# ArduinoZero.net
KiCad netlist of a schematic drawn in Altium Designer
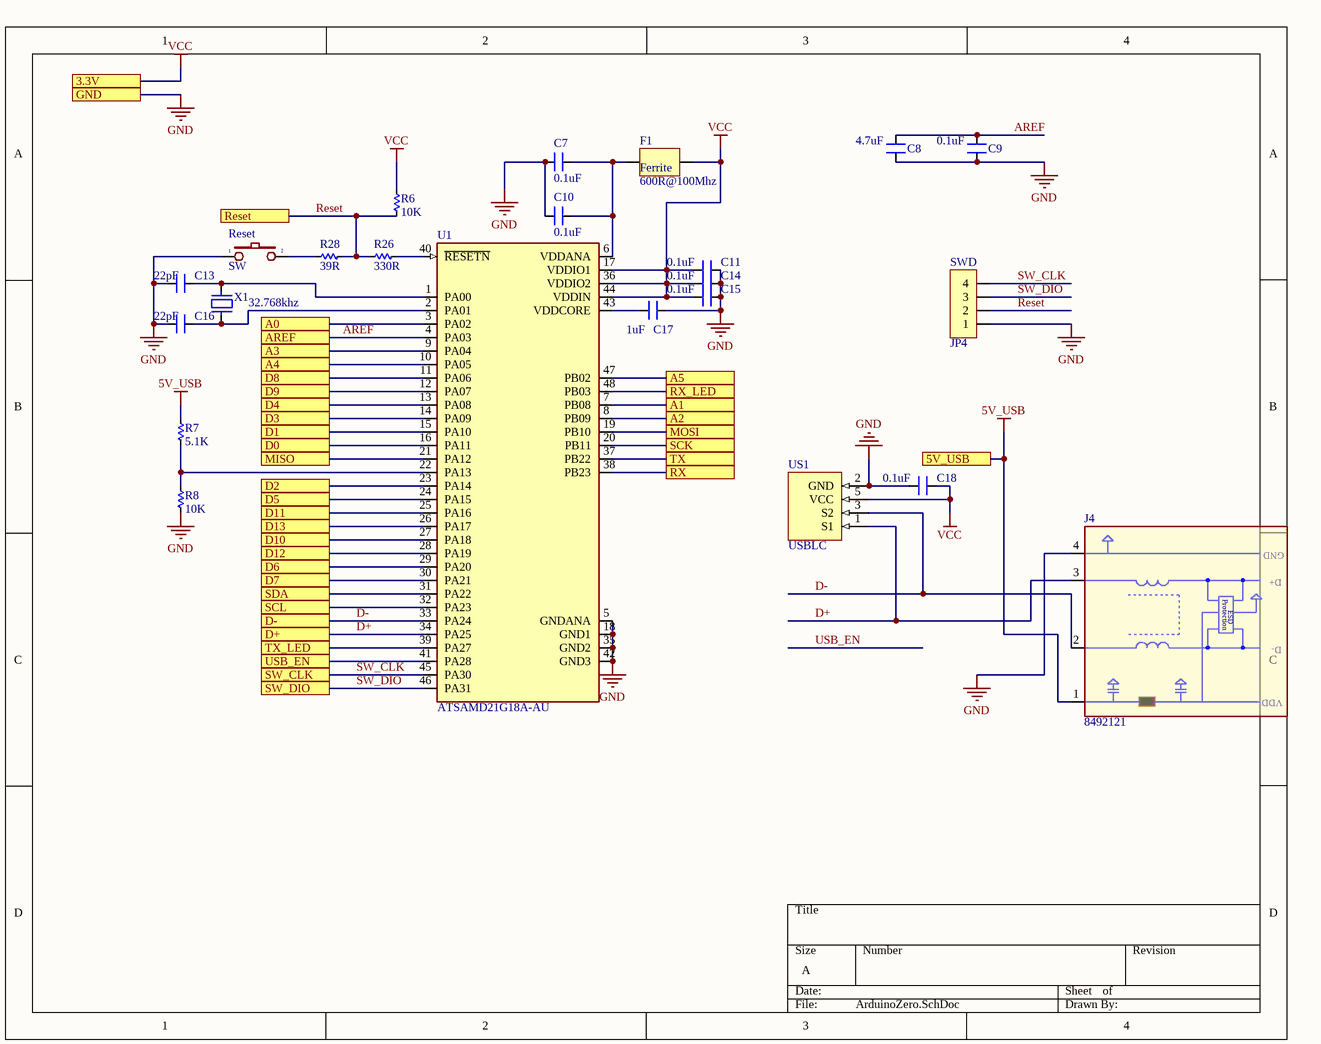
[diagram p0: ArduinoZero.SchDoc]

(export (version "E")
  (design (tool "Eeschema 10.0.6"))
  (components
    (comp (ref "C7") (value "0.1uF") (footprint "CN-SMD-0603_big") (libsource (lib "nhan") (part "CN")))
    (comp (ref "C8") (value "4.7uF") (footprint "CN-SMD-0603_big") (libsource (lib "nhan") (part "CN")))
    (comp (ref "C9") (value "0.1uF") (footprint "CN-SMD-0603_big") (libsource (lib "nhan") (part "CN")))
    (comp (ref "C10") (value "0.1uF") (footprint "CN-SMD-0603_big") (libsource (lib "nhan") (part "CN")))
    (comp (ref "C11") (value "0.1uF") (footprint "CN-SMD-0603_big") (libsource (lib "nhan") (part "CN")))
    (comp (ref "C13") (value "22pF") (footprint "CN-SMD-0603_big") (libsource (lib "nhan") (part "CN")))
    (comp (ref "C14") (value "0.1uF") (footprint "CN-SMD-0603_big") (libsource (lib "nhan") (part "CN")))
    (comp (ref "C15") (value "0.1uF") (footprint "CN-SMD-0603_big") (libsource (lib "nhan") (part "CN")))
    (comp (ref "C16") (value "22pF") (footprint "CN-SMD-0603_big") (libsource (lib "nhan") (part "CN")))
    (comp (ref "C17") (value "1uF") (footprint "CN-SMD-0603_big") (libsource (lib "nhan") (part "CN")))
    (comp (ref "C18") (value "0.1uF") (footprint "CN-SMD-0603_big") (libsource (lib "nhan") (part "CN")))
    (comp (ref "F1")
      (value "600R@100Mhz")
      (footprint "Capacitor_805")
      (libsource (lib "nhan") (part "Ferrite"))
    )
    (comp (ref "J4")
      (value "8492121")
      (footprint "USB-C3")
      (description "THT USB 2.0 A Connector WE-EPLE")
      (fields
        (field (name "MANUFACTURER") "Würth Elektronik eiSos GmbH")
        (field (name "CREATED BY") "Christin Otto")
      )
      (libsource (lib "BanLinhKien") (part "USB-4"))
    )
    (comp (ref "R6") (value "10K") (footprint "RES-SMD-0603_BIG") (libsource (lib "nhan") (part "R")))
    (comp (ref "R7") (value "5.1K") (footprint "RES-SMD-0603_BIG") (libsource (lib "nhan") (part "R")))
    (comp (ref "R8") (value "10K") (footprint "RES-SMD-0603_BIG") (libsource (lib "nhan") (part "R")))
    (comp (ref "R26") (value "330R") (footprint "RES-SMD-0603_BIG") (libsource (lib "nhan") (part "R")))
    (comp (ref "R28") (value "39R") (footprint "RES-SMD-0603_BIG") (libsource (lib "nhan") (part "R")))
    (comp (ref "Reset")
      (value "SW")
      (footprint "SW1-SMD")
      (description "Switch button 2 pin")
      (libsource (lib "BanLinhKien") (part "SW2"))
    )
    (comp (ref "SWD")
      (value "JP4")
      (footprint "JP4-D1C")
      (description "WR-PHD 2.54 mm Angled Socket Header")
      (fields
        (field (name "MANUFACTURER") "Würth Elektronik eiSos GmbH")
        (field (name "PARTNO") "613004143121")
        (field (name "CREATED BY") "Karrer Zheng")
      )
      (libsource (lib "BanLinhKien") (part "JP4"))
    )
    (comp (ref "U1")
      (value "ATSAMD21G18A-AU")
      (footprint "QFP50P900X900X120-48N")
      (fields (field (name "MF") "Microchip"))
      (libsource (lib "nhan") (part "ATSAMD21G18A-AU"))
    )
    (comp (ref "US1")
      (value "USBLC")
      (footprint "SOT23-6")
      (description "http://robocon.vn/detail/ic81-ic-dan-ul26-usblc6-2sc6-sot-23-6-st-st-esd.html")
      (libsource (lib "nhan") (part "USBLC6-2S"))
    )
    (comp (ref "X1")
      (value "32.768khz")
      (footprint "XT32k")
      (description "Crystal, 32.768 KHz, -40 to 85 degC, 3.2 x 1.5 x 0.9 mm SMD")
      (libsource (lib "BanLinhKien") (part "XT2"))
    )
  )
  (nets
    (net (code "1") (name "/A0") (class "Default")
      (node (ref "U1") (pin "3") (pinfunction "PA02_3") (pintype "bidirectional"))
    )
    (net (code "2") (name "/A1") (class "Default")
      (node (ref "U1") (pin "7") (pinfunction "PB08_7") (pintype "bidirectional"))
    )
    (net (code "3") (name "/A2") (class "Default")
      (node (ref "U1") (pin "8") (pinfunction "PB09_8") (pintype "bidirectional"))
    )
    (net (code "4") (name "/A3") (class "Default")
      (node (ref "U1") (pin "9") (pinfunction "PA04_9") (pintype "bidirectional"))
    )
    (net (code "5") (name "/A4") (class "Default")
      (node (ref "U1") (pin "10") (pinfunction "PA05_10") (pintype "bidirectional"))
    )
    (net (code "6") (name "/A5") (class "Default")
      (node (ref "U1") (pin "47") (pinfunction "PB02_47") (pintype "bidirectional"))
    )
    (net (code "7") (name "/AREF") (class "Default")
      (node (ref "C8") (pin "2") (pinfunction "2_2") (pintype "passive"))
      (node (ref "C9") (pin "2") (pinfunction "2_2") (pintype "passive"))
      (node (ref "U1") (pin "4") (pinfunction "PA03_4") (pintype "bidirectional"))
    )
    (net (code "8") (name "/D+") (class "Default")
      (node (ref "J4") (pin "3") (pinfunction "D+_3") (pintype "passive"))
      (node (ref "U1") (pin "34") (pinfunction "PA25_34") (pintype "bidirectional"))
      (node (ref "US1") (pin "1") (pinfunction "S1_1") (pintype "input"))
    )
    (net (code "9") (name "/D-") (class "Default")
      (node (ref "J4") (pin "2") (pinfunction "D-_2") (pintype "passive"))
      (node (ref "U1") (pin "33") (pinfunction "PA24_33") (pintype "bidirectional"))
      (node (ref "US1") (pin "3") (pinfunction "S2_3") (pintype "input"))
    )
    (net (code "10") (name "/D0") (class "Default")
      (node (ref "U1") (pin "16") (pinfunction "PA11_16") (pintype "bidirectional"))
    )
    (net (code "11") (name "/D1") (class "Default")
      (node (ref "U1") (pin "15") (pinfunction "PA10_15") (pintype "bidirectional"))
    )
    (net (code "12") (name "/D2") (class "Default")
      (node (ref "U1") (pin "23") (pinfunction "PA14_23") (pintype "bidirectional"))
    )
    (net (code "13") (name "/D3") (class "Default")
      (node (ref "U1") (pin "14") (pinfunction "PA09_14") (pintype "bidirectional"))
    )
    (net (code "14") (name "/D4") (class "Default")
      (node (ref "U1") (pin "13") (pinfunction "PA08_13") (pintype "bidirectional"))
    )
    (net (code "15") (name "/D5") (class "Default")
      (node (ref "U1") (pin "24") (pinfunction "PA15_24") (pintype "bidirectional"))
    )
    (net (code "16") (name "/D6") (class "Default")
      (node (ref "U1") (pin "29") (pinfunction "PA20_29") (pintype "bidirectional"))
    )
    (net (code "17") (name "/D7") (class "Default")
      (node (ref "U1") (pin "30") (pinfunction "PA21_30") (pintype "bidirectional"))
    )
    (net (code "18") (name "/D8") (class "Default")
      (node (ref "U1") (pin "11") (pinfunction "PA06_11") (pintype "bidirectional"))
    )
    (net (code "19") (name "/D9") (class "Default")
      (node (ref "U1") (pin "12") (pinfunction "PA07_12") (pintype "bidirectional"))
    )
    (net (code "20") (name "/D10") (class "Default")
      (node (ref "U1") (pin "27") (pinfunction "PA18_27") (pintype "bidirectional"))
    )
    (net (code "21") (name "/D11") (class "Default")
      (node (ref "U1") (pin "25") (pinfunction "PA16_25") (pintype "bidirectional"))
    )
    (net (code "22") (name "/D12") (class "Default")
      (node (ref "U1") (pin "28") (pinfunction "PA19_28") (pintype "bidirectional"))
    )
    (net (code "23") (name "/D13") (class "Default")
      (node (ref "U1") (pin "26") (pinfunction "PA17_26") (pintype "bidirectional"))
    )
    (net (code "24") (name "/MISO") (class "Default")
      (node (ref "U1") (pin "21") (pinfunction "PA12_21") (pintype "bidirectional"))
    )
    (net (code "25") (name "/MOSI") (class "Default")
      (node (ref "U1") (pin "19") (pinfunction "PB10_19") (pintype "bidirectional"))
    )
    (net (code "26") (name "/RX") (class "Default")
      (node (ref "U1") (pin "38") (pinfunction "PB23_38") (pintype "bidirectional"))
    )
    (net (code "27") (name "/RX_LED") (class "Default")
      (node (ref "U1") (pin "48") (pinfunction "PB03_48") (pintype "bidirectional"))
    )
    (net (code "28") (name "/Reset") (class "Default")
      (node (ref "R26") (pin "1") (pinfunction "1_1") (pintype "passive"))
      (node (ref "R28") (pin "2") (pinfunction "2_2") (pintype "passive"))
      (node (ref "R6") (pin "2") (pinfunction "2_2") (pintype "passive"))
      (node (ref "SWD") (pin "2") (pinfunction "2_2") (pintype "passive"))
    )
    (net (code "29") (name "/SCK") (class "Default")
      (node (ref "U1") (pin "20") (pinfunction "PB11_20") (pintype "bidirectional"))
    )
    (net (code "30") (name "/SCL") (class "Default")
      (node (ref "U1") (pin "32") (pinfunction "PA23_32") (pintype "bidirectional"))
    )
    (net (code "31") (name "/SDA") (class "Default")
      (node (ref "U1") (pin "31") (pinfunction "PA22_31") (pintype "bidirectional"))
    )
    (net (code "32") (name "/SW_CLK") (class "Default")
      (node (ref "SWD") (pin "4") (pinfunction "4_4") (pintype "passive"))
      (node (ref "U1") (pin "45") (pinfunction "PA30_45") (pintype "bidirectional"))
    )
    (net (code "33") (name "/SW_DIO") (class "Default")
      (node (ref "SWD") (pin "3") (pinfunction "3_3") (pintype "passive"))
      (node (ref "U1") (pin "46") (pinfunction "PA31_46") (pintype "bidirectional"))
    )
    (net (code "34") (name "/TX") (class "Default")
      (node (ref "U1") (pin "37") (pinfunction "PB22_37") (pintype "bidirectional"))
    )
    (net (code "35") (name "/TX_LED") (class "Default")
      (node (ref "U1") (pin "39") (pinfunction "PA27_39") (pintype "bidirectional"))
    )
    (net (code "36") (name "/USB_EN") (class "Default")
      (node (ref "U1") (pin "41") (pinfunction "PA28_41") (pintype "bidirectional"))
    )
    (net (code "37") (name "5V_USB") (class "Default")
      (node (ref "J4") (pin "1") (pinfunction "VBUS_1") (pintype "passive"))
      (node (ref "R7") (pin "1") (pinfunction "1_1") (pintype "passive"))
    )
    (net (code "38") (name "GND") (class "Default")
      (node (ref "C10") (pin "2") (pinfunction "2_2") (pintype "passive"))
      (node (ref "C11") (pin "2") (pinfunction "2_2") (pintype "passive"))
      (node (ref "C13") (pin "1") (pinfunction "1_1") (pintype "passive"))
      (node (ref "C14") (pin "2") (pinfunction "2_2") (pintype "passive"))
      (node (ref "C15") (pin "2") (pinfunction "2_2") (pintype "passive"))
      (node (ref "C16") (pin "1") (pinfunction "1_1") (pintype "passive"))
      (node (ref "C17") (pin "2") (pinfunction "2_2") (pintype "passive"))
      (node (ref "C18") (pin "1") (pinfunction "1_1") (pintype "passive"))
      (node (ref "C7") (pin "2") (pinfunction "2_2") (pintype "passive"))
      (node (ref "C8") (pin "1") (pinfunction "1_1") (pintype "passive"))
      (node (ref "C9") (pin "1") (pinfunction "1_1") (pintype "passive"))
      (node (ref "J4") (pin "4") (pinfunction "GND_4") (pintype "passive"))
      (node (ref "R8") (pin "2") (pinfunction "2_2") (pintype "passive"))
      (node (ref "Reset") (pin "1") (pinfunction "1_1") (pintype "passive"))
      (node (ref "SWD") (pin "1") (pinfunction "1_1") (pintype "passive"))
      (node (ref "U1") (pin "18") (pinfunction "GND1_18") (pintype "power_in"))
      (node (ref "U1") (pin "35") (pinfunction "GND2_35") (pintype "power_in"))
      (node (ref "U1") (pin "42") (pinfunction "GND3_42") (pintype "power_in"))
      (node (ref "U1") (pin "5") (pinfunction "GNDANA_5") (pintype "power_in"))
      (node (ref "US1") (pin "2") (pinfunction "GND_2") (pintype "input"))
    )
    (net (code "39") (name "Net-(R28-Pad1)") (class "Default")
      (node (ref "R28") (pin "1") (pinfunction "1_1") (pintype "passive"))
      (node (ref "Reset") (pin "2") (pinfunction "2_2") (pintype "passive"))
    )
    (net (code "40") (name "Net-(U1-PA00)") (class "Default")
      (node (ref "C13") (pin "2") (pinfunction "2_2") (pintype "passive"))
      (node (ref "U1") (pin "1") (pinfunction "PA00_1") (pintype "bidirectional"))
      (node (ref "X1") (pin "2") (pinfunction "2_2") (pintype "passive"))
    )
    (net (code "41") (name "Net-(U1-PA01)") (class "Default")
      (node (ref "C16") (pin "2") (pinfunction "2_2") (pintype "passive"))
      (node (ref "U1") (pin "2") (pinfunction "PA01_2") (pintype "bidirectional"))
      (node (ref "X1") (pin "1") (pinfunction "1_1") (pintype "passive"))
    )
    (net (code "42") (name "Net-(U1-PA13)") (class "Default")
      (node (ref "R7") (pin "2") (pinfunction "2_2") (pintype "passive"))
      (node (ref "R8") (pin "1") (pinfunction "1_1") (pintype "passive"))
      (node (ref "U1") (pin "22") (pinfunction "PA13_22") (pintype "bidirectional"))
    )
    (net (code "43") (name "Net-(U1-VDDANA)") (class "Default")
      (node (ref "C10") (pin "1") (pinfunction "1_1") (pintype "passive"))
      (node (ref "C7") (pin "1") (pinfunction "1_1") (pintype "passive"))
      (node (ref "F1") (pin "1") (pinfunction "1_1") (pintype "passive"))
      (node (ref "U1") (pin "6") (pinfunction "VDDANA_6") (pintype "power_in"))
    )
    (net (code "44") (name "Net-(U1-VDDCORE)") (class "Default")
      (node (ref "C17") (pin "1") (pinfunction "1_1") (pintype "passive"))
      (node (ref "U1") (pin "43") (pinfunction "VDDCORE_43") (pintype "power_in"))
    )
    (net (code "45") (name "Net-(U1-~{RESETN})") (class "Default")
      (node (ref "R26") (pin "2") (pinfunction "2_2") (pintype "passive"))
      (node (ref "U1") (pin "40") (pinfunction "~{RESETN}_40") (pintype "input"))
    )
    (net (code "46") (name "VCC") (class "Default")
      (node (ref "C11") (pin "1") (pinfunction "1_1") (pintype "passive"))
      (node (ref "C14") (pin "1") (pinfunction "1_1") (pintype "passive"))
      (node (ref "C15") (pin "1") (pinfunction "1_1") (pintype "passive"))
      (node (ref "C18") (pin "2") (pinfunction "2_2") (pintype "passive"))
      (node (ref "F1") (pin "2") (pinfunction "2_2") (pintype "passive"))
      (node (ref "R6") (pin "1") (pinfunction "1_1") (pintype "passive"))
      (node (ref "U1") (pin "17") (pinfunction "VDDIO1_17") (pintype "power_in"))
      (node (ref "U1") (pin "36") (pinfunction "VDDIO2_36") (pintype "power_in"))
      (node (ref "U1") (pin "44") (pinfunction "VDDIN_44") (pintype "power_in"))
      (node (ref "US1") (pin "5") (pinfunction "VCC_5") (pintype "input"))
    )
  )
)
